# LoRaLo_V20-2.net
KiCad netlist of a schematic drawn in EAGLE
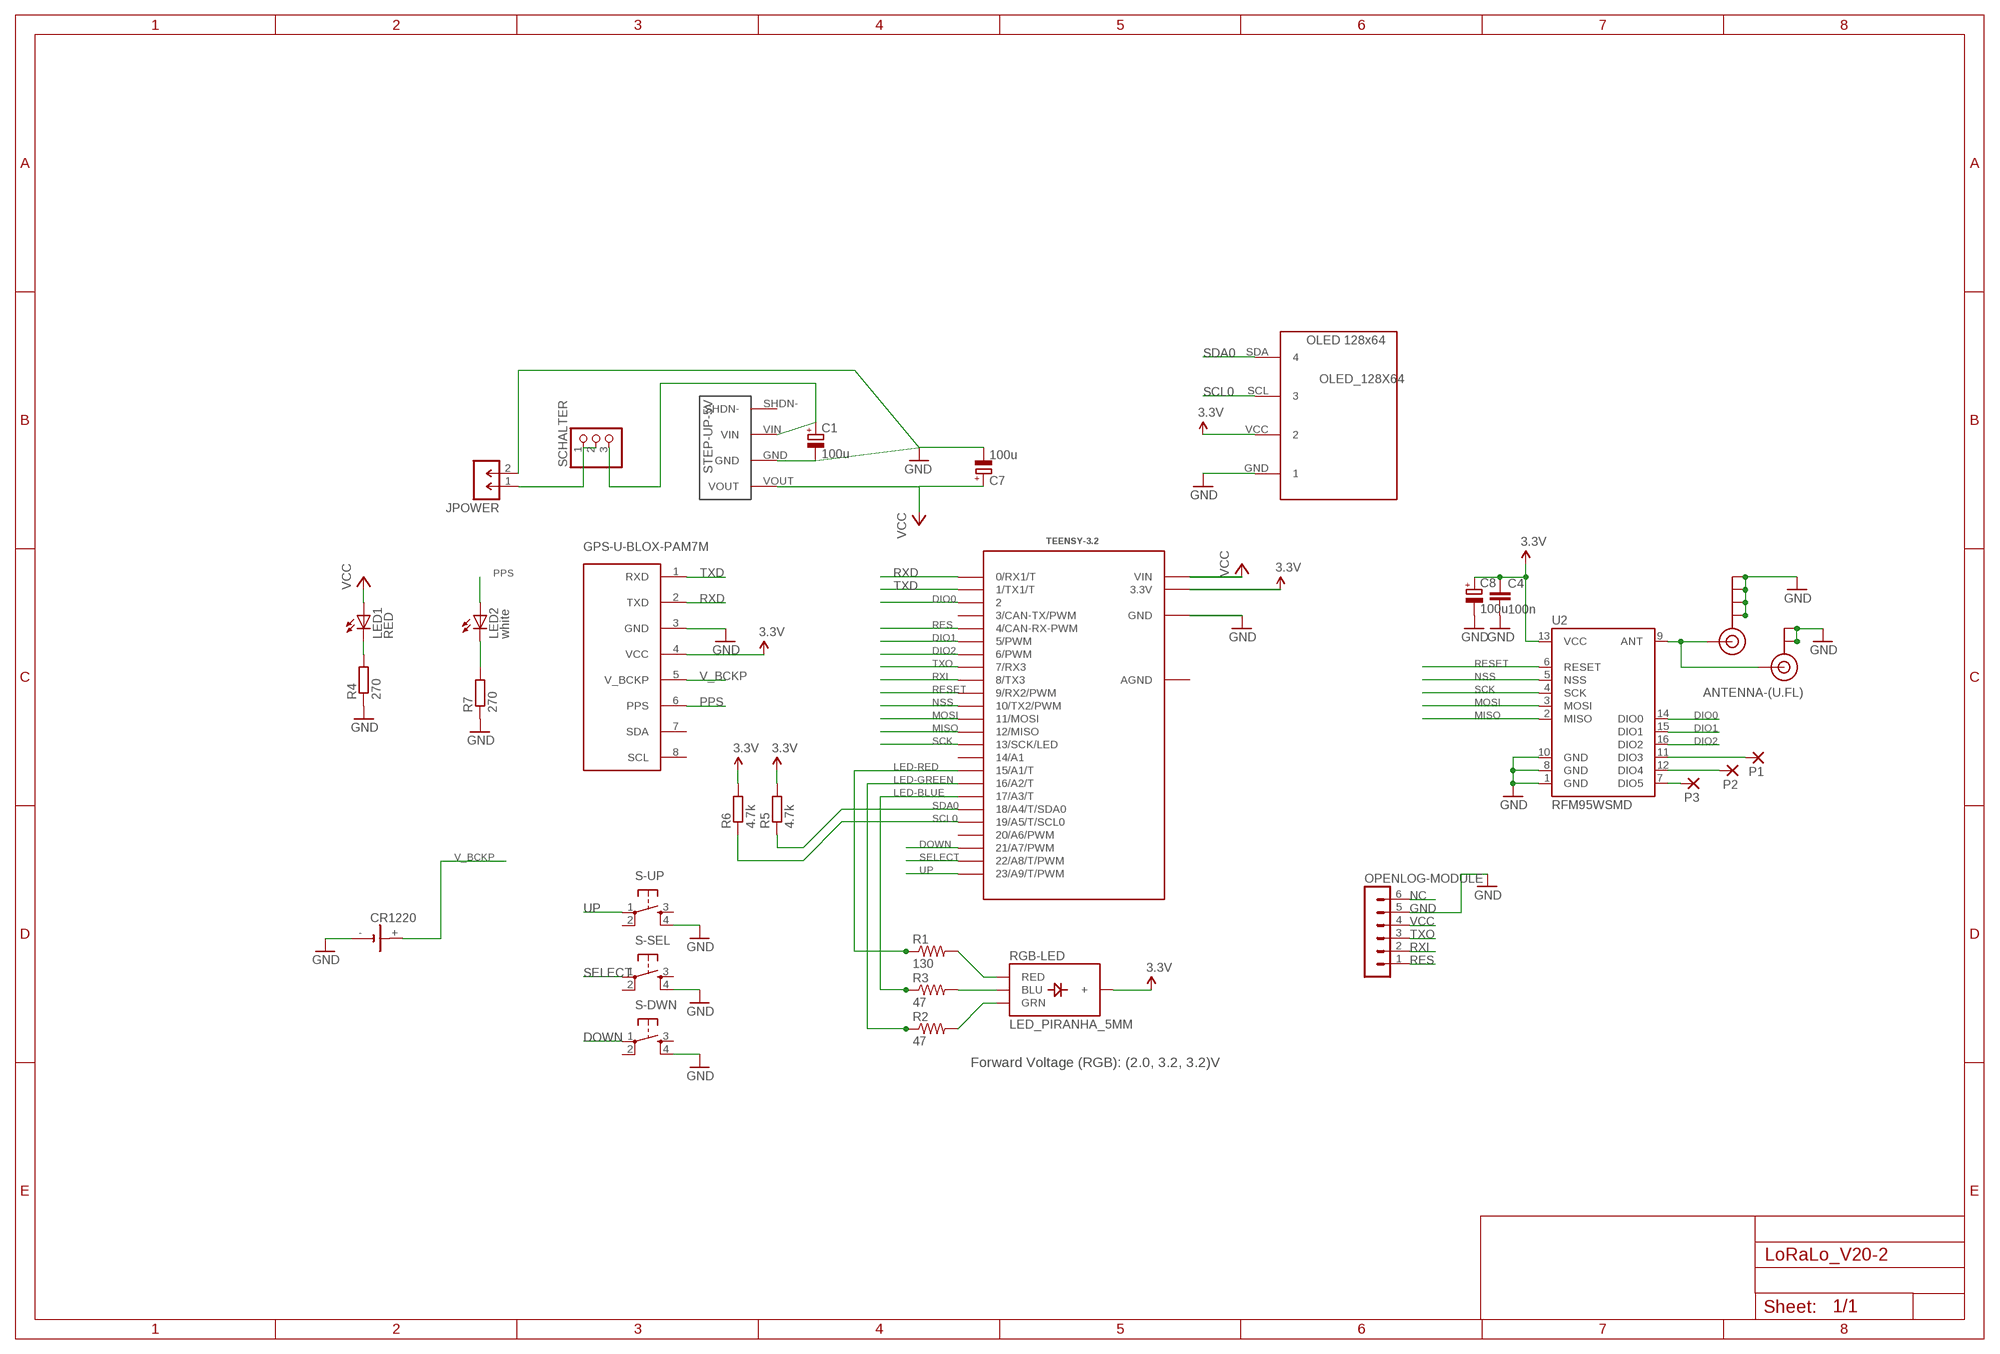
[diagram p0: schematic, sheet 1]

(export (version "E")
  (design (tool "Eeschema 10.0.6"))
  (components
    (comp (ref "ANTENNA-(EDGE-MOUNT)")
      (value "SMA_EDGE")
      (footprint "eagle-import:SMA-EDGE")
      (libsource (lib "eagle-import") (part "SMA_EDGE"))
    )
    (comp (ref "ANTENNA-(U.FL)")
      (value "U.FL")
      (footprint "eagle-import:U.FL")
      (libsource (lib "eagle-import") (part "U.FL"))
    )
    (comp (ref "C1")
      (value "100u")
      (footprint "eagle-import:PANASONIC_D")
      (libsource (lib "eagle-import") (part "CPOL-EUD"))
    )
    (comp (ref "C4")
      (value "100n")
      (footprint "eagle-import:C1206")
      (libsource (lib "eagle-import") (part "C-EUC1206"))
    )
    (comp (ref "C7")
      (value "100u")
      (footprint "eagle-import:PANASONIC_D")
      (libsource (lib "eagle-import") (part "CPOL-EUD"))
    )
    (comp (ref "C8")
      (value "100u")
      (footprint "eagle-import:PANASONIC_D")
      (libsource (lib "eagle-import") (part "CPOL-EUD"))
    )
    (comp (ref "CR1220")
      (value "CH291-1220LF")
      (footprint "eagle-import:CH291-1220LF")
      (libsource (lib "eagle-import") (part "CH291-1220LF"))
    )
    (comp (ref "GPS-U-BLOX-PAM7M")
      (value "U-BLOX-PAM-7Q")
      (footprint "eagle-import:U-BLOX-PAM-7Q")
      (libsource (lib "eagle-import") (part "U-BLOX-PAM-7Q"))
    )
    (comp (ref "JPOWER")
      (value "M-1X02-SIP-100-40")
      (footprint "eagle-import:SIP-100-02-40")
      (libsource (lib "eagle-import") (part "M-1X02-SIP-100-40"))
    )
    (comp (ref "LED1")
      (value "RED")
      (footprint "eagle-import:LED-1206")
      (libsource (lib "eagle-import") (part "LED1206"))
    )
    (comp (ref "LED2")
      (value "white")
      (footprint "eagle-import:LED-1206")
      (libsource (lib "eagle-import") (part "LED1206"))
    )
    (comp (ref "OLED_128X64")
      (value "OLED_128X64")
      (footprint "eagle-import:OLED_128X64")
      (libsource (lib "eagle-import") (part "OLED_128X64"))
    )
    (comp (ref "OPENLOG-MODULE")
      (value "MA06-1")
      (footprint "eagle-import:MA06-1")
      (libsource (lib "eagle-import") (part "MA06-1"))
    )
    (comp (ref "P1")
      (value "1,6/0,8")
      (footprint "eagle-import:1,6_0,8")
      (libsource (lib "eagle-import") (part "1,6/0,8"))
    )
    (comp (ref "P2")
      (value "1,6/0,8")
      (footprint "eagle-import:1,6_0,8")
      (libsource (lib "eagle-import") (part "1,6/0,8"))
    )
    (comp (ref "P3")
      (value "1,6/0,8")
      (footprint "eagle-import:1,6_0,8")
      (libsource (lib "eagle-import") (part "1,6/0,8"))
    )
    (comp (ref "R1")
      (value "130")
      (footprint "eagle-import:1206")
      (libsource (lib "eagle-import") (part "RESISTOR1206"))
    )
    (comp (ref "R2")
      (value "47")
      (footprint "eagle-import:1206")
      (libsource (lib "eagle-import") (part "RESISTOR1206"))
    )
    (comp (ref "R3")
      (value "47")
      (footprint "eagle-import:1206")
      (libsource (lib "eagle-import") (part "RESISTOR1206"))
    )
    (comp (ref "R4")
      (value "270")
      (footprint "eagle-import:M1206")
      (libsource (lib "eagle-import") (part "R-EU_M1206"))
    )
    (comp (ref "R5")
      (value "4.7k")
      (footprint "eagle-import:M1206")
      (libsource (lib "eagle-import") (part "R-EU_M1206"))
    )
    (comp (ref "R6")
      (value "4.7k")
      (footprint "eagle-import:M1206")
      (libsource (lib "eagle-import") (part "R-EU_M1206"))
    )
    (comp (ref "R7")
      (value "270")
      (footprint "eagle-import:M1206")
      (libsource (lib "eagle-import") (part "R-EU_M1206"))
    )
    (comp (ref "RGB-LED")
      (value "LED_PIRANHA_5MM")
      (footprint "eagle-import:LED_PIRANHA_5MM")
      (libsource (lib "eagle-import") (part "LED_PIRANHA_5MM"))
    )
    (comp (ref "S-DWN")
      (value "TAC_SWITCHPTH")
      (footprint "eagle-import:TACTILE-PTH")
      (libsource (lib "eagle-import") (part "TAC_SWITCHPTH"))
    )
    (comp (ref "S-SEL")
      (value "TAC_SWITCHPTH")
      (footprint "eagle-import:TACTILE-PTH")
      (libsource (lib "eagle-import") (part "TAC_SWITCHPTH"))
    )
    (comp (ref "S-UP")
      (value "TAC_SWITCHPTH")
      (footprint "eagle-import:TACTILE-PTH")
      (libsource (lib "eagle-import") (part "TAC_SWITCHPTH"))
    )
    (comp (ref "SCHALTER")
      (value "PINHD-1X3")
      (footprint "eagle-import:1X03")
      (libsource (lib "eagle-import") (part "PINHD-1X3"))
    )
    (comp (ref "STEP-UP-5V")
      (value "POLOLU_STEP-UP")
      (footprint "eagle-import:POLOLU_STEP-UP")
      (libsource (lib "eagle-import") (part "POLOLU_STEP-UP"))
    )
    (comp (ref "TEENSY-3.2")
      (value "TEENSY_3.1_DIL")
      (footprint "eagle-import:TEENSY3-DIL")
      (libsource (lib "eagle-import") (part "TEENSY_3.1_DIL"))
    )
    (comp (ref "U2")
      (value "RFM95WSMD")
      (footprint "eagle-import:RFM95W_SMD")
      (libsource (lib "eagle-import") (part "RFM95WSMD"))
    )
  )
  (nets
    (net (code "1") (name "/AGND") (class "Default")
      (node (ref "TEENSY-3.2") (pin "AGND") (pinfunction "AGND_AGND") (pintype "power_in"))
    )
    (net (code "2") (name "/DIO0") (class "Default")
      (node (ref "TEENSY-3.2") (pin "2") (pinfunction "2_2") (pintype "bidirectional"))
      (node (ref "U2") (pin "14") (pinfunction "DIO0_14") (pintype "input"))
    )
    (net (code "3") (name "/DIO1") (class "Default")
      (node (ref "TEENSY-3.2") (pin "5") (pinfunction "5/PWM_5") (pintype "bidirectional"))
      (node (ref "U2") (pin "15") (pinfunction "DIO1_15") (pintype "input"))
    )
    (net (code "4") (name "/DIO2") (class "Default")
      (node (ref "TEENSY-3.2") (pin "6") (pinfunction "6/PWM_6") (pintype "bidirectional"))
      (node (ref "U2") (pin "16") (pinfunction "DIO2_16") (pintype "input"))
    )
    (net (code "5") (name "/DOWN") (class "Default")
      (node (ref "S-DWN") (pin "1") (pinfunction "1_1") (pintype "passive"))
      (node (ref "TEENSY-3.2") (pin "21/A7") (pinfunction "21/A7/PWM_21/A7") (pintype "bidirectional"))
    )
    (net (code "6") (name "/LED-BLUE") (class "Default")
      (node (ref "R3") (pin "1") (pinfunction "1_1") (pintype "passive"))
      (node (ref "TEENSY-3.2") (pin "17/A3") (pinfunction "17/A3/T_17/A3") (pintype "bidirectional"))
    )
    (net (code "7") (name "/LED-GREEN") (class "Default")
      (node (ref "R2") (pin "1") (pinfunction "1_1") (pintype "passive"))
      (node (ref "TEENSY-3.2") (pin "16/A2") (pinfunction "16/A2/T_16/A2") (pintype "bidirectional"))
    )
    (net (code "8") (name "/LED-RED") (class "Default")
      (node (ref "R1") (pin "1") (pinfunction "1_1") (pintype "passive"))
      (node (ref "TEENSY-3.2") (pin "15/A1") (pinfunction "15/A1/T_15/A1") (pintype "bidirectional"))
    )
    (net (code "9") (name "/MISO") (class "Default")
      (node (ref "TEENSY-3.2") (pin "12") (pinfunction "12/MISO_12") (pintype "bidirectional"))
      (node (ref "U2") (pin "2") (pinfunction "MISO_2") (pintype "output"))
    )
    (net (code "10") (name "/MOSI") (class "Default")
      (node (ref "TEENSY-3.2") (pin "11") (pinfunction "11/MOSI_11") (pintype "bidirectional"))
      (node (ref "U2") (pin "3") (pinfunction "MOSI_3") (pintype "input"))
    )
    (net (code "11") (name "/NC") (class "Default")
      (node (ref "OPENLOG-MODULE") (pin "6") (pinfunction "6_6") (pintype "passive"))
    )
    (net (code "12") (name "/NSS") (class "Default")
      (node (ref "TEENSY-3.2") (pin "10") (pinfunction "10/TX2/PWM_10") (pintype "bidirectional"))
      (node (ref "U2") (pin "5") (pinfunction "NSS_5") (pintype "input"))
    )
    (net (code "13") (name "/PPS") (class "Default")
      (node (ref "GPS-U-BLOX-PAM7M") (pin "6") (pinfunction "PPS_6") (pintype "bidirectional"))
      (node (ref "LED2") (pin "A") (pinfunction "A_A") (pintype "passive"))
    )
    (net (code "14") (name "/RES") (class "Default")
      (node (ref "OPENLOG-MODULE") (pin "1") (pinfunction "1_1") (pintype "passive"))
      (node (ref "TEENSY-3.2") (pin "4") (pinfunction "4/CAN-RX-PWM_4") (pintype "bidirectional"))
    )
    (net (code "15") (name "/RESET") (class "Default")
      (node (ref "TEENSY-3.2") (pin "9") (pinfunction "9/RX2/PWM_9") (pintype "bidirectional"))
      (node (ref "U2") (pin "6") (pinfunction "RESET_6") (pintype "output"))
    )
    (net (code "16") (name "/RXD") (class "Default")
      (node (ref "GPS-U-BLOX-PAM7M") (pin "2") (pinfunction "TXD_2") (pintype "bidirectional"))
      (node (ref "TEENSY-3.2") (pin "0") (pinfunction "0/RX1/T_0") (pintype "bidirectional"))
    )
    (net (code "17") (name "/RXI") (class "Default")
      (node (ref "OPENLOG-MODULE") (pin "2") (pinfunction "2_2") (pintype "passive"))
      (node (ref "TEENSY-3.2") (pin "8") (pinfunction "8/TX3_8") (pintype "bidirectional"))
    )
    (net (code "18") (name "/SCK") (class "Default")
      (node (ref "TEENSY-3.2") (pin "13") (pinfunction "13/SCK/LED_13") (pintype "bidirectional"))
      (node (ref "U2") (pin "4") (pinfunction "SCK_4") (pintype "input"))
    )
    (net (code "19") (name "/SCL0") (class "Default")
      (node (ref "OLED_128X64") (pin "SCL") (pinfunction "3_SCL") (pintype "bidirectional"))
      (node (ref "R6") (pin "1") (pinfunction "1_1") (pintype "passive"))
      (node (ref "TEENSY-3.2") (pin "19/A5") (pinfunction "19/A5/T/SCL0_19/A5") (pintype "bidirectional"))
    )
    (net (code "20") (name "/SDA0") (class "Default")
      (node (ref "OLED_128X64") (pin "SDA") (pinfunction "4_SDA") (pintype "bidirectional"))
      (node (ref "R5") (pin "1") (pinfunction "1_1") (pintype "passive"))
      (node (ref "TEENSY-3.2") (pin "18/A4") (pinfunction "18/A4/T/SDA0_18/A4") (pintype "bidirectional"))
    )
    (net (code "21") (name "/SELECT") (class "Default")
      (node (ref "S-SEL") (pin "1") (pinfunction "1_1") (pintype "passive"))
      (node (ref "TEENSY-3.2") (pin "22/A8") (pinfunction "22/A8/T/PWM_22/A8") (pintype "bidirectional"))
    )
    (net (code "22") (name "/TXD") (class "Default")
      (node (ref "GPS-U-BLOX-PAM7M") (pin "1") (pinfunction "RXD_1") (pintype "bidirectional"))
      (node (ref "TEENSY-3.2") (pin "1") (pinfunction "1/TX1/T_1") (pintype "bidirectional"))
    )
    (net (code "23") (name "/TXO") (class "Default")
      (node (ref "OPENLOG-MODULE") (pin "3") (pinfunction "3_3") (pintype "passive"))
      (node (ref "TEENSY-3.2") (pin "7") (pinfunction "7/RX3_7") (pintype "bidirectional"))
    )
    (net (code "24") (name "/UP") (class "Default")
      (node (ref "S-UP") (pin "1") (pinfunction "1_1") (pintype "passive"))
      (node (ref "TEENSY-3.2") (pin "23/A9") (pinfunction "23/A9/T/PWM_23/A9") (pintype "bidirectional"))
    )
    (net (code "25") (name "/V_BCKP") (class "Default")
      (node (ref "CR1220") (pin "+") (pinfunction "+_+") (pintype "passive"))
      (node (ref "GPS-U-BLOX-PAM7M") (pin "5") (pinfunction "V_BCKP_5") (pintype "bidirectional"))
    )
    (net (code "26") (name "3.3V") (class "Default")
      (node (ref "C4") (pin "1") (pinfunction "1_1") (pintype "passive"))
      (node (ref "C8") (pin "+") (pinfunction "+_+") (pintype "passive"))
      (node (ref "GPS-U-BLOX-PAM7M") (pin "4") (pinfunction "VCC_4") (pintype "bidirectional"))
      (node (ref "OLED_128X64") (pin "VCC") (pinfunction "2_VCC") (pintype "bidirectional"))
      (node (ref "R5") (pin "2") (pinfunction "2_2") (pintype "passive"))
      (node (ref "R6") (pin "2") (pinfunction "2_2") (pintype "passive"))
      (node (ref "RGB-LED") (pin "+") (pinfunction "+_+") (pintype "bidirectional"))
      (node (ref "TEENSY-3.2") (pin "3.3V") (pinfunction "3.3V_3.3V") (pintype "power_in"))
      (node (ref "U2") (pin "13") (pinfunction "VCC_13") (pintype "bidirectional"))
    )
    (net (code "27") (name "GND") (class "Default")
      (node (ref "ANTENNA-(EDGE-MOUNT)") (pin "GND@0") (pinfunction "GND_GND@0") (pintype "bidirectional"))
      (node (ref "ANTENNA-(EDGE-MOUNT)") (pin "GND@1") (pinfunction "GND_GND@1") (pintype "bidirectional"))
      (node (ref "ANTENNA-(EDGE-MOUNT)") (pin "GND@2") (pinfunction "GND_GND@2") (pintype "bidirectional"))
      (node (ref "ANTENNA-(EDGE-MOUNT)") (pin "GND@3") (pinfunction "GND_GND@3") (pintype "bidirectional"))
      (node (ref "ANTENNA-(U.FL)") (pin "P$1") (pinfunction "GND_P$1") (pintype "bidirectional"))
      (node (ref "ANTENNA-(U.FL)") (pin "P$2") (pinfunction "GND_P$2") (pintype "bidirectional"))
      (node (ref "C1") (pin "-") (pinfunction "-_-") (pintype "passive"))
      (node (ref "C4") (pin "2") (pinfunction "2_2") (pintype "passive"))
      (node (ref "C7") (pin "-") (pinfunction "-_-") (pintype "passive"))
      (node (ref "C8") (pin "-") (pinfunction "-_-") (pintype "passive"))
      (node (ref "CR1220") (pin "-") (pinfunction "-_-") (pintype "passive"))
      (node (ref "GPS-U-BLOX-PAM7M") (pin "3") (pinfunction "GND_3") (pintype "bidirectional"))
      (node (ref "JPOWER") (pin "2") (pinfunction "2_2") (pintype "passive"))
      (node (ref "OLED_128X64") (pin "GND") (pinfunction "1_GND") (pintype "bidirectional"))
      (node (ref "OPENLOG-MODULE") (pin "5") (pinfunction "5_5") (pintype "passive"))
      (node (ref "R4") (pin "1") (pinfunction "1_1") (pintype "passive"))
      (node (ref "R7") (pin "1") (pinfunction "1_1") (pintype "passive"))
      (node (ref "S-DWN") (pin "4") (pinfunction "4_4") (pintype "passive"))
      (node (ref "S-SEL") (pin "4") (pinfunction "4_4") (pintype "passive"))
      (node (ref "S-UP") (pin "4") (pinfunction "4_4") (pintype "passive"))
      (node (ref "STEP-UP-5V") (pin "GND") (pinfunction "GND_GND") (pintype "bidirectional"))
      (node (ref "TEENSY-3.2") (pin "GND") (pinfunction "GND_GND") (pintype "power_in"))
      (node (ref "U2") (pin "1") (pinfunction "GND_1") (pintype "power_in"))
      (node (ref "U2") (pin "10") (pinfunction "GND_10") (pintype "power_in"))
      (node (ref "U2") (pin "8") (pinfunction "GND_8") (pintype "power_in"))
    )
    (net (code "28") (name "Net-(ANTENNA-(EDGE-MOUNT)-SIGNAL)") (class "Default")
      (node (ref "ANTENNA-(EDGE-MOUNT)") (pin "SIG") (pinfunction "SIGNAL_SIG") (pintype "bidirectional"))
      (node (ref "ANTENNA-(U.FL)") (pin "P$3") (pinfunction "SIGNAL_P$3") (pintype "bidirectional"))
      (node (ref "U2") (pin "9") (pinfunction "ANT_9") (pintype "bidirectional"))
    )
    (net (code "29") (name "Net-(C1-Pad+)") (class "Default")
      (node (ref "C1") (pin "+") (pinfunction "+_+") (pintype "passive"))
      (node (ref "SCHALTER") (pin "3") (pinfunction "3_3") (pintype "passive"))
      (node (ref "STEP-UP-5V") (pin "VIN") (pinfunction "VIN_VIN") (pintype "bidirectional"))
    )
    (net (code "30") (name "Net-(JPOWER-Pad1)") (class "Default")
      (node (ref "JPOWER") (pin "1") (pinfunction "1_1") (pintype "passive"))
      (node (ref "SCHALTER") (pin "1") (pinfunction "1_1") (pintype "passive"))
      (node (ref "SCHALTER") (pin "2") (pinfunction "2_2") (pintype "passive"))
    )
    (net (code "31") (name "Net-(LED1-PadC)") (class "Default")
      (node (ref "LED1") (pin "C") (pinfunction "C_C") (pintype "passive"))
      (node (ref "R4") (pin "2") (pinfunction "2_2") (pintype "passive"))
    )
    (net (code "32") (name "Net-(LED2-PadC)") (class "Default")
      (node (ref "LED2") (pin "C") (pinfunction "C_C") (pintype "passive"))
      (node (ref "R7") (pin "2") (pinfunction "2_2") (pintype "passive"))
    )
    (net (code "33") (name "Net-(P1-P)") (class "Default")
      (node (ref "P1") (pin "1") (pinfunction "P_1") (pintype "passive"))
      (node (ref "U2") (pin "11") (pinfunction "DIO3_11") (pintype "bidirectional"))
    )
    (net (code "34") (name "Net-(P2-P)") (class "Default")
      (node (ref "P2") (pin "1") (pinfunction "P_1") (pintype "passive"))
      (node (ref "U2") (pin "12") (pinfunction "DIO4_12") (pintype "bidirectional"))
    )
    (net (code "35") (name "Net-(P3-P)") (class "Default")
      (node (ref "P3") (pin "1") (pinfunction "P_1") (pintype "passive"))
      (node (ref "U2") (pin "7") (pinfunction "DIO5_7") (pintype "bidirectional"))
    )
    (net (code "36") (name "Net-(RGB-LED-BLU)") (class "Default")
      (node (ref "R3") (pin "2") (pinfunction "2_2") (pintype "passive"))
      (node (ref "RGB-LED") (pin "B") (pinfunction "BLU_B") (pintype "bidirectional"))
    )
    (net (code "37") (name "Net-(RGB-LED-GRN)") (class "Default")
      (node (ref "R2") (pin "2") (pinfunction "2_2") (pintype "passive"))
      (node (ref "RGB-LED") (pin "G") (pinfunction "GRN_G") (pintype "bidirectional"))
    )
    (net (code "38") (name "Net-(RGB-LED-RED)") (class "Default")
      (node (ref "R1") (pin "2") (pinfunction "2_2") (pintype "passive"))
      (node (ref "RGB-LED") (pin "R") (pinfunction "RED_R") (pintype "bidirectional"))
    )
    (net (code "39") (name "VCC") (class "Default")
      (node (ref "C7") (pin "+") (pinfunction "+_+") (pintype "passive"))
      (node (ref "LED1") (pin "A") (pinfunction "A_A") (pintype "passive"))
      (node (ref "OPENLOG-MODULE") (pin "4") (pinfunction "4_4") (pintype "passive"))
      (node (ref "STEP-UP-5V") (pin "VOUT") (pinfunction "VOUT_VOUT") (pintype "bidirectional"))
      (node (ref "TEENSY-3.2") (pin "VIN") (pinfunction "VIN_VIN") (pintype "power_in"))
    )
    (net (code "40") (name "unconnected-(GPS-U-BLOX-PAM7M-SCL-Pad8)") (class "Default")
      (node (ref "GPS-U-BLOX-PAM7M") (pin "8") (pinfunction "SCL_8") (pintype "bidirectional"))
    )
    (net (code "41") (name "unconnected-(GPS-U-BLOX-PAM7M-SDA-Pad7)") (class "Default")
      (node (ref "GPS-U-BLOX-PAM7M") (pin "7") (pinfunction "SDA_7") (pintype "bidirectional"))
    )
    (net (code "42") (name "unconnected-(S-DWN-Pad2)") (class "Default")
      (node (ref "S-DWN") (pin "2") (pinfunction "2_2") (pintype "passive"))
    )
    (net (code "43") (name "unconnected-(S-DWN-Pad3)") (class "Default")
      (node (ref "S-DWN") (pin "3") (pinfunction "3_3") (pintype "passive"))
    )
    (net (code "44") (name "unconnected-(S-SEL-Pad2)") (class "Default")
      (node (ref "S-SEL") (pin "2") (pinfunction "2_2") (pintype "passive"))
    )
    (net (code "45") (name "unconnected-(S-SEL-Pad3)") (class "Default")
      (node (ref "S-SEL") (pin "3") (pinfunction "3_3") (pintype "passive"))
    )
    (net (code "46") (name "unconnected-(S-UP-Pad2)") (class "Default")
      (node (ref "S-UP") (pin "2") (pinfunction "2_2") (pintype "passive"))
    )
    (net (code "47") (name "unconnected-(S-UP-Pad3)") (class "Default")
      (node (ref "S-UP") (pin "3") (pinfunction "3_3") (pintype "passive"))
    )
    (net (code "48") (name "unconnected-(STEP-UP-5V-PadSHDN-)") (class "Default")
      (node (ref "STEP-UP-5V") (pin "SHDN-") (pinfunction "SHDN-_SHDN-") (pintype "bidirectional"))
    )
    (net (code "49") (name "unconnected-(TEENSY-3.2-3{slash}CAN-TX{slash}PWM-Pad3)") (class "Default")
      (node (ref "TEENSY-3.2") (pin "3") (pinfunction "3/CAN-TX/PWM_3") (pintype "bidirectional"))
    )
    (net (code "50") (name "unconnected-(TEENSY-3.2-14{slash}A1-Pad14{slash}A0)") (class "Default")
      (node (ref "TEENSY-3.2") (pin "14/A0") (pinfunction "14/A1_14/A0") (pintype "bidirectional"))
    )
    (net (code "51") (name "unconnected-(TEENSY-3.2-20{slash}A6{slash}PWM-Pad20{slash}A6)") (class "Default")
      (node (ref "TEENSY-3.2") (pin "20/A6") (pinfunction "20/A6/PWM_20/A6") (pintype "bidirectional"))
    )
  )
)
